# Dveri_Zapaishek.net
KiCad netlist of a schematic drawn in EAGLE
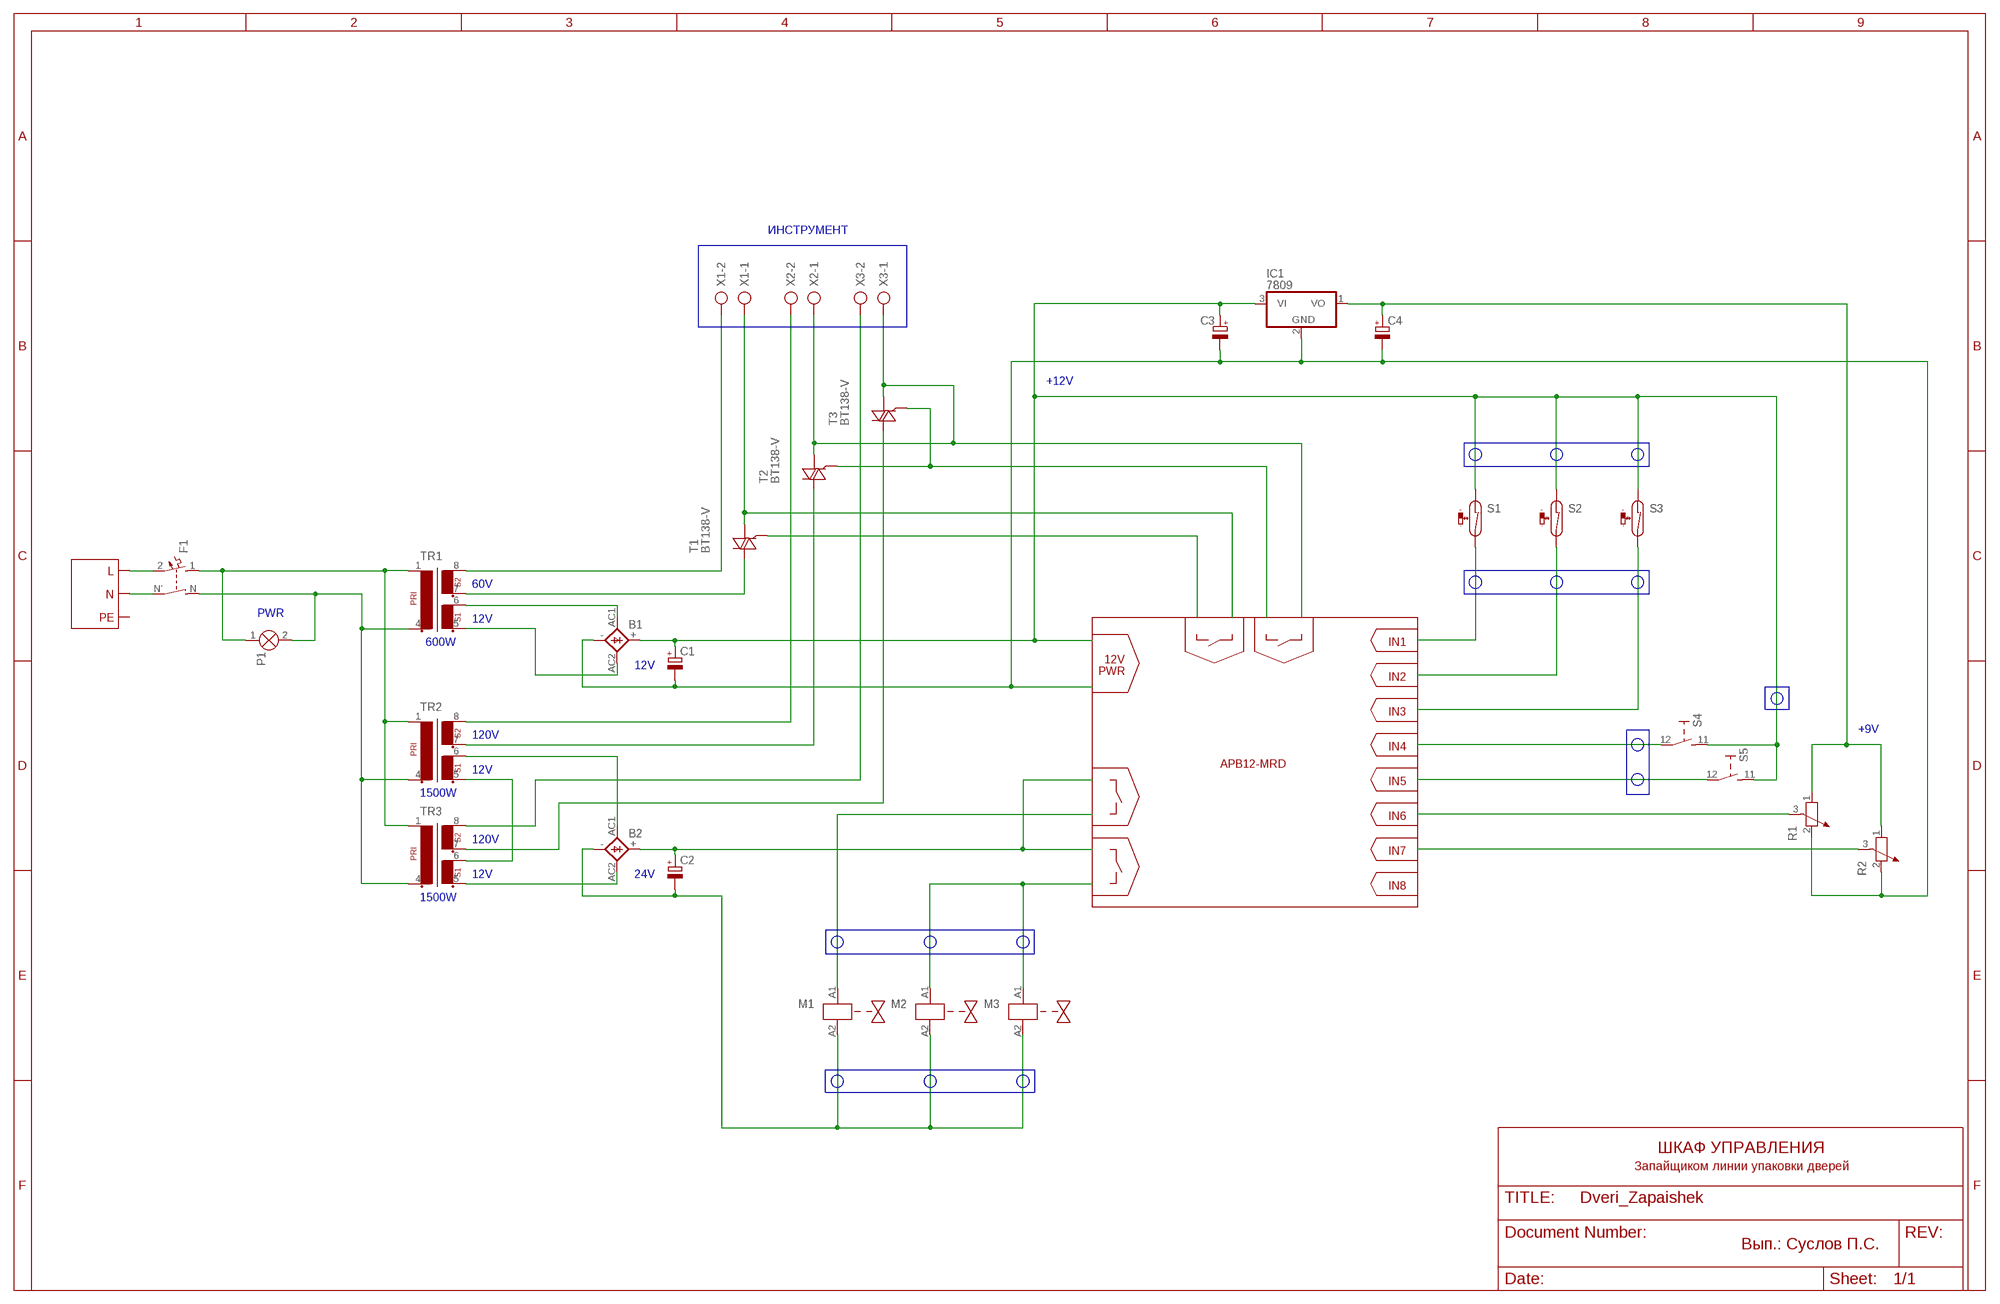
[diagram p0: schematic, sheet 1]

(export (version "E")
  (design (tool "Eeschema 10.0.6"))
  (components
    (comp (ref "B1")
      (value "2KBP")
      (footprint "eagle-import:2KBP")
      (libsource (lib "eagle-import") (part "2KBP"))
    )
    (comp (ref "B2")
      (value "2KBP")
      (footprint "eagle-import:2KBP")
      (libsource (lib "eagle-import") (part "2KBP"))
    )
    (comp (ref "C1")
      (value "CPOL-EUE3.5-10")
      (footprint "eagle-import:E3,5-10")
      (libsource (lib "eagle-import") (part "CPOL-EUE3.5-10"))
    )
    (comp (ref "C2")
      (value "CPOL-EUE3.5-10")
      (footprint "eagle-import:E3,5-10")
      (libsource (lib "eagle-import") (part "CPOL-EUE3.5-10"))
    )
    (comp (ref "C3")
      (value "CPOL-EUE3.5-10")
      (footprint "eagle-import:E3,5-10")
      (libsource (lib "eagle-import") (part "CPOL-EUE3.5-10"))
    )
    (comp (ref "C4")
      (value "CPOL-EUE3.5-10")
      (footprint "eagle-import:E3,5-10")
      (libsource (lib "eagle-import") (part "CPOL-EUE3.5-10"))
    )
    (comp (ref "F1")
      (value "LEITUNGSSCHUTZSCHALTER_2-POL")
      (footprint "eagle-import:LEITUNGSSCHUTZSCHALTER_2-POL")
      (libsource (lib "eagle-import") (part "LEITUNGSSCHUTZSCHALTER_2-POL"))
    )
    (comp (ref "IC1")
      (value "7809")
      (footprint "eagle-import:TO92")
      (libsource (lib "eagle-import") (part "78L08"))
    )
    (comp (ref "M1")
      (value "ELEKTROMAG_BETAETIGTES_MAGNETVENTIL_PNEUMATIK_HYDRAULIK")
      (footprint "eagle-import:MAGNETVENTIL_PNEUMATIK-HYDRAULIK")
      (libsource (lib "eagle-import") (part "ELEKTROMAG_BETAETIGTES_MAGNETVENTIL_PNEUMATIK_HYDRAULIK"))
    )
    (comp (ref "M2")
      (value "ELEKTROMAG_BETAETIGTES_MAGNETVENTIL_PNEUMATIK_HYDRAULIK")
      (footprint "eagle-import:MAGNETVENTIL_PNEUMATIK-HYDRAULIK")
      (libsource (lib "eagle-import") (part "ELEKTROMAG_BETAETIGTES_MAGNETVENTIL_PNEUMATIK_HYDRAULIK"))
    )
    (comp (ref "M3")
      (value "ELEKTROMAG_BETAETIGTES_MAGNETVENTIL_PNEUMATIK_HYDRAULIK")
      (footprint "eagle-import:MAGNETVENTIL_PNEUMATIK-HYDRAULIK")
      (libsource (lib "eagle-import") (part "ELEKTROMAG_BETAETIGTES_MAGNETVENTIL_PNEUMATIK_HYDRAULIK"))
    )
    (comp (ref "P1")
      (value "SIGNALLAMPE")
      (footprint "eagle-import:LAMPE")
      (libsource (lib "eagle-import") (part "SIGNALLAMPE"))
    )
    (comp (ref "R1")
      (value "POTENTIOMETER_PT-10")
      (footprint "eagle-import:PT-10")
      (libsource (lib "eagle-import") (part "POTENTIOMETER_PT-10"))
    )
    (comp (ref "R2")
      (value "POTENTIOMETER_PT-10")
      (footprint "eagle-import:PT-10")
      (libsource (lib "eagle-import") (part "POTENTIOMETER_PT-10"))
    )
    (comp (ref "S1")
      (value "REED-SWITCH-CT10-1530-G1")
      (footprint "eagle-import:CT10-G1")
      (fields (field (name "MF") "COTO TECHNOLOGY") (field (name "MPN") "CT10-1530-G1"))
      (libsource (lib "eagle-import") (part "REED-SWITCH-CT10-1530-G1"))
    )
    (comp (ref "S2")
      (value "REED-SWITCH-CT10-1530-G1")
      (footprint "eagle-import:CT10-G1")
      (fields (field (name "MF") "COTO TECHNOLOGY") (field (name "MPN") "CT10-1530-G1"))
      (libsource (lib "eagle-import") (part "REED-SWITCH-CT10-1530-G1"))
    )
    (comp (ref "S3")
      (value "REED-SWITCH-CT10-1530-G1")
      (footprint "eagle-import:CT10-G1")
      (fields (field (name "MF") "COTO TECHNOLOGY") (field (name "MPN") "CT10-1530-G1"))
      (libsource (lib "eagle-import") (part "REED-SWITCH-CT10-1530-G1"))
    )
    (comp (ref "S4")
      (value "SCHALTER_SCHLIESSER_HANDBETAETIGT")
      (footprint "eagle-import:KIPPSCHALTER_AUS")
      (libsource (lib "eagle-import") (part "SCHALTER_SCHLIESSER_HANDBETAETIGT"))
    )
    (comp (ref "S5")
      (value "SCHALTER_SCHLIESSER_HANDBETAETIGT")
      (footprint "eagle-import:KIPPSCHALTER_AUS")
      (libsource (lib "eagle-import") (part "SCHALTER_SCHLIESSER_HANDBETAETIGT"))
    )
    (comp (ref "T1")
      (value "BT138-V")
      (footprint "eagle-import:TO220BV")
      (libsource (lib "eagle-import") (part "BT138-V"))
    )
    (comp (ref "T2")
      (value "BT138-V")
      (footprint "eagle-import:TO220BV")
      (libsource (lib "eagle-import") (part "BT138-V"))
    )
    (comp (ref "T3")
      (value "BT138-V")
      (footprint "eagle-import:TO220BV")
      (libsource (lib "eagle-import") (part "BT138-V"))
    )
    (comp (ref "TR1")
      (value "EE20-2")
      (footprint "eagle-import:EE20-2")
      (libsource (lib "eagle-import") (part "EE20-2"))
    )
    (comp (ref "TR2")
      (value "EE20-2")
      (footprint "eagle-import:EE20-2")
      (libsource (lib "eagle-import") (part "EE20-2"))
    )
    (comp (ref "TR3")
      (value "EE20-2")
      (footprint "eagle-import:EE20-2")
      (libsource (lib "eagle-import") (part "EE20-2"))
    )
    (comp (ref "X1")
      (value "AK500/2")
      (footprint "eagle-import:AK500_2")
      (libsource (lib "eagle-import") (part "AK500/2"))
    )
    (comp (ref "X2")
      (value "AK500/2")
      (footprint "eagle-import:AK500_2")
      (libsource (lib "eagle-import") (part "AK500/2"))
    )
    (comp (ref "X3")
      (value "AK500/2")
      (footprint "eagle-import:AK500_2")
      (libsource (lib "eagle-import") (part "AK500/2"))
    )
  )
  (nets
    (net (code "2") (name "Net-(B2-Pad+)") (class "Default")
      (node (ref "B2") (pin "+") (pinfunction "+_+") (pintype "passive"))
      (node (ref "C2") (pin "+") (pinfunction "+_+") (pintype "passive"))
    )
    (net (code "3") (name "Net-(B2-Pad-)") (class "Default")
      (node (ref "B2") (pin "-") (pinfunction "-_-") (pintype "passive"))
      (node (ref "C2") (pin "-") (pinfunction "-_-") (pintype "passive"))
      (node (ref "M1") (pin "A2") (pinfunction "A2_A2") (pintype "input"))
      (node (ref "M2") (pin "A2") (pinfunction "A2_A2") (pintype "input"))
      (node (ref "M3") (pin "A2") (pinfunction "A2_A2") (pintype "input"))
    )
    (net (code "4") (name "Net-(F1-N-PadN')") (class "Default")
      (node (ref "F1") (pin "N'") (pinfunction "N_N'") (pintype "passive"))
    )
    (net (code "5") (name "Net-(F1-Pad2)") (class "Default")
      (node (ref "F1") (pin "2") (pinfunction "2_2") (pintype "passive"))
    )
    (net (code "6") (name "Net-(IC1-GND)") (class "Default")
      (node (ref "B1") (pin "-") (pinfunction "-_-") (pintype "passive"))
      (node (ref "C1") (pin "-") (pinfunction "-_-") (pintype "passive"))
      (node (ref "C3") (pin "-") (pinfunction "-_-") (pintype "passive"))
      (node (ref "C4") (pin "-") (pinfunction "-_-") (pintype "passive"))
      (node (ref "IC1") (pin "2") (pinfunction "GND_2") (pintype "passive"))
      (node (ref "R1") (pin "2") (pinfunction "2_2") (pintype "passive"))
      (node (ref "R2") (pin "2") (pinfunction "2_2") (pintype "passive"))
    )
    (net (code "7") (name "Net-(IC1-VI)") (class "Default")
      (node (ref "B1") (pin "+") (pinfunction "+_+") (pintype "passive"))
      (node (ref "C1") (pin "+") (pinfunction "+_+") (pintype "passive"))
      (node (ref "C3") (pin "+") (pinfunction "+_+") (pintype "passive"))
      (node (ref "IC1") (pin "3") (pinfunction "VI_3") (pintype "input"))
      (node (ref "S1") (pin "1") (pinfunction "1_1") (pintype "passive"))
      (node (ref "S2") (pin "1") (pinfunction "1_1") (pintype "passive"))
      (node (ref "S3") (pin "1") (pinfunction "1_1") (pintype "passive"))
      (node (ref "S4") (pin "11") (pinfunction "CS1_11") (pintype "passive"))
      (node (ref "S5") (pin "11") (pinfunction "CS1_11") (pintype "passive"))
    )
    (net (code "8") (name "Net-(IC1-VO)") (class "Default")
      (node (ref "C4") (pin "+") (pinfunction "+_+") (pintype "passive"))
      (node (ref "IC1") (pin "1") (pinfunction "VO_1") (pintype "passive"))
      (node (ref "R1") (pin "1") (pinfunction "1_1") (pintype "passive"))
      (node (ref "R2") (pin "1") (pinfunction "1_1") (pintype "passive"))
    )
    (net (code "9") (name "Net-(M2-PadA1)") (class "Default")
      (node (ref "M2") (pin "A1") (pinfunction "A1_A1") (pintype "input"))
      (node (ref "M3") (pin "A1") (pinfunction "A1_A1") (pintype "input"))
    )
    (net (code "10") (name "Net-(P1-X1)") (class "Default")
      (node (ref "F1") (pin "1") (pinfunction "1_1") (pintype "passive"))
      (node (ref "P1") (pin "1") (pinfunction "X1_1") (pintype "passive"))
      (node (ref "TR1") (pin "1") (pinfunction "1_1") (pintype "passive"))
      (node (ref "TR2") (pin "1") (pinfunction "1_1") (pintype "passive"))
      (node (ref "TR3") (pin "1") (pinfunction "1_1") (pintype "passive"))
    )
    (net (code "11") (name "Net-(P1-X2)") (class "Default")
      (node (ref "F1") (pin "N") (pinfunction "N_N") (pintype "passive"))
      (node (ref "P1") (pin "2") (pinfunction "X2_2") (pintype "passive"))
      (node (ref "TR1") (pin "4") (pinfunction "2_4") (pintype "passive"))
      (node (ref "TR2") (pin "4") (pinfunction "2_4") (pintype "passive"))
      (node (ref "TR3") (pin "4") (pinfunction "2_4") (pintype "passive"))
    )
    (net (code "12") (name "Net-(T1-A1)") (class "Default")
      (node (ref "T1") (pin "T1") (pinfunction "A1_T1") (pintype "passive"))
      (node (ref "X1") (pin "1") (pinfunction "KL_1") (pintype "passive"))
    )
    (net (code "13") (name "Net-(T1-A2)") (class "Default")
      (node (ref "T1") (pin "T2") (pinfunction "A2_T2") (pintype "passive"))
      (node (ref "TR1") (pin "7") (pinfunction "5_7") (pintype "passive"))
    )
    (net (code "14") (name "Net-(T2-A1)") (class "Default")
      (node (ref "T2") (pin "T1") (pinfunction "A1_T1") (pintype "passive"))
      (node (ref "T3") (pin "T1") (pinfunction "A1_T1") (pintype "passive"))
      (node (ref "X2") (pin "1") (pinfunction "KL_1") (pintype "passive"))
      (node (ref "X3") (pin "1") (pinfunction "KL_1") (pintype "passive"))
    )
    (net (code "15") (name "Net-(T2-A2)") (class "Default")
      (node (ref "T2") (pin "T2") (pinfunction "A2_T2") (pintype "passive"))
      (node (ref "TR2") (pin "7") (pinfunction "5_7") (pintype "passive"))
    )
    (net (code "16") (name "Net-(T2-PadG)") (class "Default")
      (node (ref "T2") (pin "G") (pinfunction "G_G") (pintype "passive"))
      (node (ref "T3") (pin "G") (pinfunction "G_G") (pintype "passive"))
    )
    (net (code "17") (name "Net-(T3-A2)") (class "Default")
      (node (ref "T3") (pin "T2") (pinfunction "A2_T2") (pintype "passive"))
      (node (ref "TR3") (pin "7") (pinfunction "5_7") (pintype "passive"))
    )
    (net (code "18") (name "Net-(TR1-3)") (class "Default")
      (node (ref "B1") (pin "AC2") (pinfunction "AC2_AC2") (pintype "passive"))
      (node (ref "TR1") (pin "5") (pinfunction "3_5") (pintype "passive"))
    )
    (net (code "19") (name "Net-(TR1-4)") (class "Default")
      (node (ref "B1") (pin "AC1") (pinfunction "AC1_AC1") (pintype "passive"))
      (node (ref "TR1") (pin "6") (pinfunction "4_6") (pintype "passive"))
    )
    (net (code "20") (name "Net-(TR1-6)") (class "Default")
      (node (ref "TR1") (pin "8") (pinfunction "6_8") (pintype "passive"))
      (node (ref "X1") (pin "2") (pinfunction "KL_2") (pintype "passive"))
    )
    (net (code "21") (name "Net-(TR2-3)") (class "Default")
      (node (ref "TR2") (pin "5") (pinfunction "3_5") (pintype "passive"))
      (node (ref "TR3") (pin "6") (pinfunction "4_6") (pintype "passive"))
    )
    (net (code "22") (name "Net-(TR2-4)") (class "Default")
      (node (ref "B2") (pin "AC1") (pinfunction "AC1_AC1") (pintype "passive"))
      (node (ref "TR2") (pin "6") (pinfunction "4_6") (pintype "passive"))
    )
    (net (code "23") (name "Net-(TR2-6)") (class "Default")
      (node (ref "TR2") (pin "8") (pinfunction "6_8") (pintype "passive"))
      (node (ref "X2") (pin "2") (pinfunction "KL_2") (pintype "passive"))
    )
    (net (code "24") (name "Net-(TR3-3)") (class "Default")
      (node (ref "B2") (pin "AC2") (pinfunction "AC2_AC2") (pintype "passive"))
      (node (ref "TR3") (pin "5") (pinfunction "3_5") (pintype "passive"))
    )
    (net (code "25") (name "Net-(TR3-6)") (class "Default")
      (node (ref "TR3") (pin "8") (pinfunction "6_8") (pintype "passive"))
      (node (ref "X3") (pin "2") (pinfunction "KL_2") (pintype "passive"))
    )
    (net (code "26") (name "unconnected-(M1-PadA1)") (class "Default")
      (node (ref "M1") (pin "A1") (pinfunction "A1_A1") (pintype "input"))
    )
    (net (code "27") (name "unconnected-(R1-Pad3)") (class "Default")
      (node (ref "R1") (pin "3") (pinfunction "3_3") (pintype "passive"))
    )
    (net (code "28") (name "unconnected-(R2-Pad3)") (class "Default")
      (node (ref "R2") (pin "3") (pinfunction "3_3") (pintype "passive"))
    )
    (net (code "29") (name "unconnected-(S1-Pad2)") (class "Default")
      (node (ref "S1") (pin "2") (pinfunction "2_2") (pintype "passive"))
    )
    (net (code "30") (name "unconnected-(S2-Pad2)") (class "Default")
      (node (ref "S2") (pin "2") (pinfunction "2_2") (pintype "passive"))
    )
    (net (code "31") (name "unconnected-(S3-Pad2)") (class "Default")
      (node (ref "S3") (pin "2") (pinfunction "2_2") (pintype "passive"))
    )
    (net (code "32") (name "unconnected-(S4-S1-Pad12)") (class "Default")
      (node (ref "S4") (pin "12") (pinfunction "S1_12") (pintype "passive"))
    )
    (net (code "33") (name "unconnected-(S5-S1-Pad12)") (class "Default")
      (node (ref "S5") (pin "12") (pinfunction "S1_12") (pintype "passive"))
    )
    (net (code "34") (name "unconnected-(T1-PadG)") (class "Default")
      (node (ref "T1") (pin "G") (pinfunction "G_G") (pintype "passive"))
    )
  )
)
